# lionpuffer-04.net
KiCad netlist of a schematic drawn in EAGLE
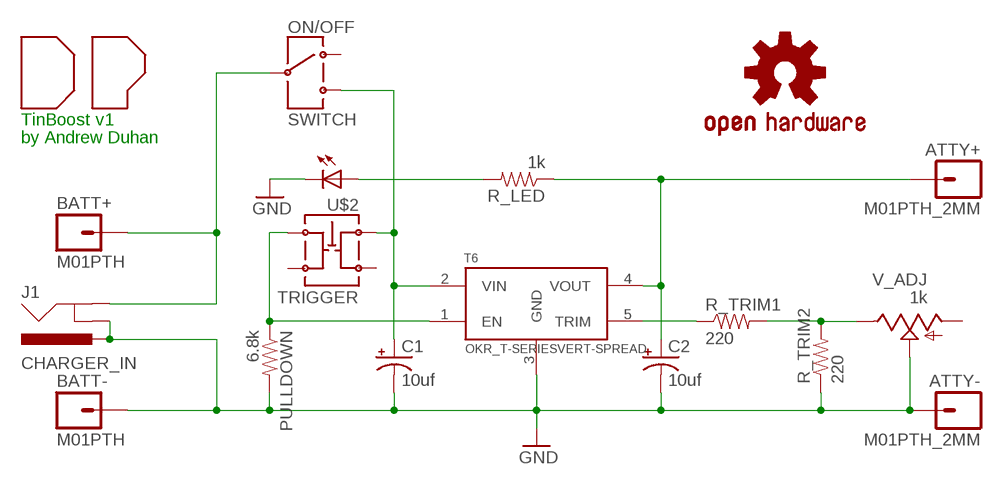
[diagram p0: schematic, sheet 1]

(export (version "E")
  (design (tool "Eeschema 10.0.6"))
  (components
    (comp (ref "ATTY+")
      (value "M01PTH_2MM")
      (footprint "eagle-import:1X01_2MM")
      (libsource (lib "eagle-import") (part "SparkFun-Connectors_M01PTH_2MM"))
    )
    (comp (ref "ATTY-")
      (value "M01PTH_2MM")
      (footprint "eagle-import:1X01_2MM")
      (libsource (lib "eagle-import") (part "SparkFun-Connectors_M01PTH_2MM"))
    )
    (comp (ref "BATT+")
      (value "M01PTH")
      (footprint "eagle-import:1X01")
      (libsource (lib "eagle-import") (part "M01PTH"))
    )
    (comp (ref "BATT-")
      (value "M01PTH")
      (footprint "eagle-import:1X01")
      (libsource (lib "eagle-import") (part "M01PTH"))
    )
    (comp (ref "C1")
      (value "10uf")
      (footprint "eagle-import:CPOL-RADIAL-10UF-25V")
      (libsource (lib "eagle-import") (part "CAP_POLPTH2"))
    )
    (comp (ref "C2")
      (value "10uf")
      (footprint "eagle-import:CPOL-RADIAL-10UF-25V")
      (libsource (lib "eagle-import") (part "CAP_POLPTH2"))
    )
    (comp (ref "J1")
      (value "CHARGER_IN")
      (footprint "eagle-import:POWER_JACK_PTH")
      (libsource (lib "eagle-import") (part "POWER_JACKPTH"))
    )
    (comp (ref "ON/OFF")
      (value "SWITCH")
      (footprint "eagle-import:SWITCH-CK1101")
      (libsource (lib "eagle-import") (part "SWITCH-SPSTCK-1101"))
    )
    (comp (ref "PULLDOWN")
      (value "6.8k")
      (footprint "eagle-import:1_6W-RES")
      (libsource (lib "eagle-import") (part "RESISTORPTH-1/6W"))
    )
    (comp (ref "R_LED")
      (value "1k")
      (footprint "eagle-import:1_6W-RES")
      (libsource (lib "eagle-import") (part "RESISTORPTH-1/6W"))
    )
    (comp (ref "R_TRIM1")
      (value "220")
      (footprint "eagle-import:1_6W-RES")
      (libsource (lib "eagle-import") (part "RESISTORPTH-1/6W"))
    )
    (comp (ref "R_TRIM2")
      (value "220")
      (footprint "eagle-import:1_6W-RES")
      (libsource (lib "eagle-import") (part "RESISTORPTH-1/6W"))
    )
    (comp (ref "T6")
      (value "OKR_T-SERIESVERT-SPREAD")
      (footprint "eagle-import:OKR-T_6_10-VERT-SPACED")
      (libsource (lib "eagle-import") (part "OKR_T-SERIESVERT-SPREAD"))
    )
    (comp (ref "U$1")
      (value "OSHW-LOGOM")
      (footprint "eagle-import:OSHW-LOGO-M")
      (libsource (lib "eagle-import") (part "OSHW-LOGOM"))
    )
    (comp (ref "U$2")
      (value "TRIGGER")
      (footprint "eagle-import:E-SWITCH_TL1250")
      (libsource (lib "eagle-import") (part "SWITCH-TACT-ILL"))
    )
    (comp (ref "U$3")
      (value "DP_LOGO")
      (footprint "eagle-import:DP_LOGO")
      (libsource (lib "eagle-import") (part "DP_LOGO"))
    )
    (comp (ref "V_ADJ")
      (value "1k")
      (footprint "eagle-import:POT-TOP-BOURNS")
      (libsource (lib "eagle-import") (part "POT3310Y-001"))
    )
  )
  (nets
    (net (code "1") (name "GND") (class "Default")
      (node (ref "ATTY-") (pin "1") (pinfunction "1_1") (pintype "passive"))
      (node (ref "BATT-") (pin "1") (pinfunction "1_1") (pintype "passive"))
      (node (ref "C1") (pin "2") (pinfunction "-_2") (pintype "passive"))
      (node (ref "C2") (pin "2") (pinfunction "-_2") (pintype "passive"))
      (node (ref "J1") (pin "GNDBREAK") (pinfunction "GNDBREAK_GNDBREAK") (pintype "bidirectional"))
      (node (ref "J1") (pin "PWR") (pinfunction "PWR_PWR") (pintype "bidirectional"))
      (node (ref "PULLDOWN") (pin "2") (pinfunction "2_2") (pintype "passive"))
      (node (ref "R_TRIM2") (pin "1") (pinfunction "1_1") (pintype "passive"))
      (node (ref "T6") (pin "3") (pinfunction "GND_3") (pintype "bidirectional"))
      (node (ref "U$2") (pin "5") (pinfunction "C_5") (pintype "passive"))
      (node (ref "V_ADJ") (pin "2") (pinfunction "W_2") (pintype "passive"))
    )
    (net (code "2") (name "Net-(BATT+-Pad1)") (class "Default")
      (node (ref "BATT+") (pin "1") (pinfunction "1_1") (pintype "passive"))
      (node (ref "J1") (pin "GND") (pinfunction "GND_GND") (pintype "bidirectional"))
      (node (ref "ON/OFF") (pin "2") (pinfunction "2_2") (pintype "bidirectional"))
    )
    (net (code "3") (name "Net-(C1-+)") (class "Default")
      (node (ref "C1") (pin "1") (pinfunction "+_1") (pintype "passive"))
      (node (ref "ON/OFF") (pin "3") (pinfunction "3_3") (pintype "bidirectional"))
      (node (ref "T6") (pin "2") (pinfunction "VIN_2") (pintype "bidirectional"))
      (node (ref "U$2") (pin "1") (pinfunction "1_1") (pintype "bidirectional"))
    )
    (net (code "4") (name "Net-(C2-+)") (class "Default")
      (node (ref "ATTY+") (pin "1") (pinfunction "1_1") (pintype "passive"))
      (node (ref "C2") (pin "1") (pinfunction "+_1") (pintype "passive"))
      (node (ref "R_LED") (pin "1") (pinfunction "1_1") (pintype "passive"))
      (node (ref "T6") (pin "4") (pinfunction "VOUT_4") (pintype "bidirectional"))
    )
    (net (code "5") (name "Net-(T6-EN)") (class "Default")
      (node (ref "PULLDOWN") (pin "1") (pinfunction "1_1") (pintype "passive"))
      (node (ref "T6") (pin "1") (pinfunction "EN_1") (pintype "bidirectional"))
      (node (ref "U$2") (pin "3") (pinfunction "3_3") (pintype "bidirectional"))
    )
    (net (code "6") (name "Net-(T6-TRIM)") (class "Default")
      (node (ref "R_TRIM1") (pin "1") (pinfunction "1_1") (pintype "passive"))
      (node (ref "T6") (pin "5") (pinfunction "TRIM_5") (pintype "bidirectional"))
    )
    (net (code "7") (name "Net-(U$2-A)") (class "Default")
      (node (ref "R_LED") (pin "2") (pinfunction "2_2") (pintype "passive"))
      (node (ref "U$2") (pin "6") (pinfunction "A_6") (pintype "passive"))
    )
    (net (code "8") (name "Net-(V_ADJ-B)") (class "Default")
      (node (ref "R_TRIM1") (pin "2") (pinfunction "2_2") (pintype "passive"))
      (node (ref "R_TRIM2") (pin "2") (pinfunction "2_2") (pintype "passive"))
      (node (ref "V_ADJ") (pin "3") (pinfunction "B_3") (pintype "passive"))
    )
    (net (code "9") (name "unconnected-(ON/OFF-Pad1)") (class "Default")
      (node (ref "ON/OFF") (pin "1") (pinfunction "1_1") (pintype "bidirectional"))
    )
    (net (code "10") (name "unconnected-(U$2-Pad2)") (class "Default")
      (node (ref "U$2") (pin "2") (pinfunction "2_2") (pintype "bidirectional"))
    )
    (net (code "11") (name "unconnected-(U$2-Pad4)") (class "Default")
      (node (ref "U$2") (pin "4") (pinfunction "4_4") (pintype "bidirectional"))
    )
    (net (code "12") (name "unconnected-(V_ADJ-A-Pad1)") (class "Default")
      (node (ref "V_ADJ") (pin "1") (pinfunction "A_1") (pintype "passive"))
    )
  )
)
